# nrfdongle.net
KiCad netlist of a schematic drawn in EAGLE
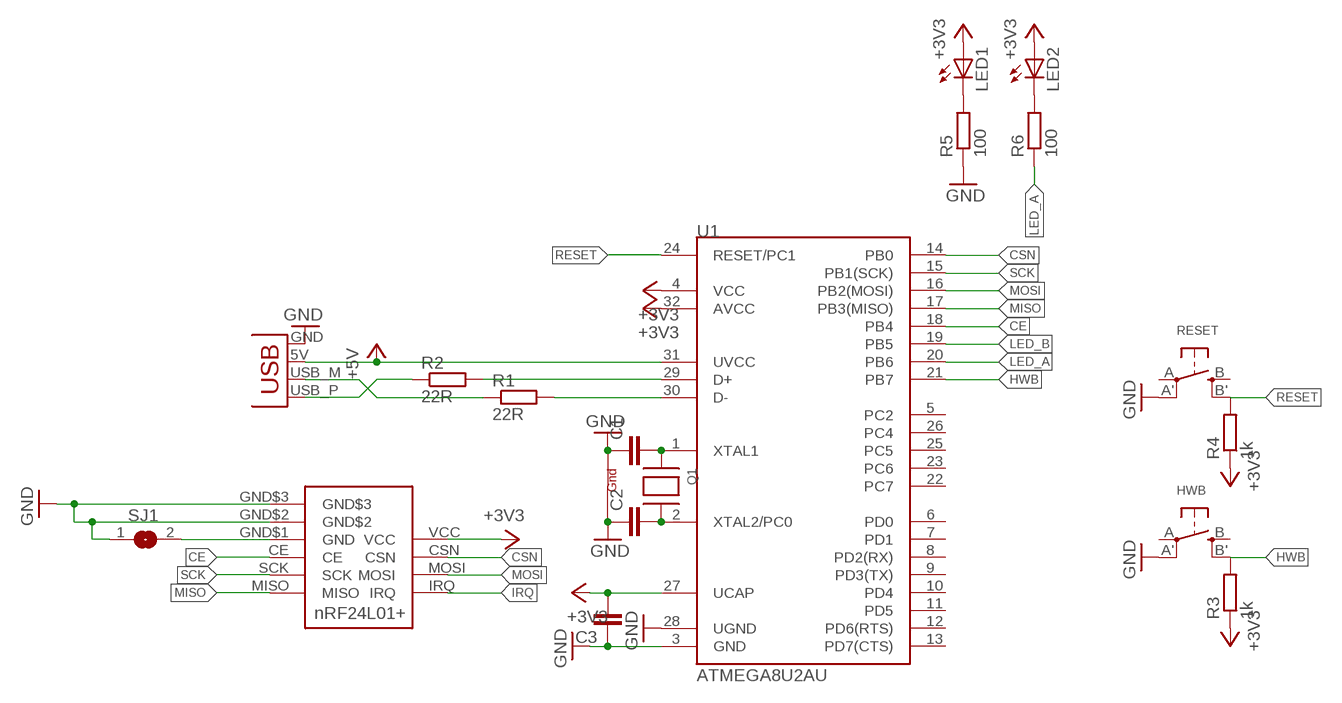
[diagram p0: schematic, sheet 1]

(export (version "E")
  (design (tool "Eeschema 10.0.6"))
  (components
    (comp (ref "C1")
      (value "C-EUC0805")
      (footprint "eagle-import:C0805")
      (libsource (lib "eagle-import") (part "C-EUC0805"))
    )
    (comp (ref "C2")
      (value "C-EUC0805")
      (footprint "eagle-import:C0805")
      (libsource (lib "eagle-import") (part "C-EUC0805"))
    )
    (comp (ref "C3")
      (value "C-EUC0805")
      (footprint "eagle-import:C0805")
      (libsource (lib "eagle-import") (part "C-EUC0805"))
    )
    (comp (ref "CHINESE1")
      (value "NRF24L01+CHINESE-DUAL")
      (footprint "eagle-import:CHINESE-DUALPINOUT")
      (libsource (lib "eagle-import") (part "NRF24L01+CHINESE-DUAL"))
    )
    (comp (ref "HWB")
      (value "SWITCH_TACT_SMT")
      (footprint "eagle-import:EVQ-Q2")
      (libsource (lib "eagle-import") (part "SWITCH_TACT_SMT"))
    )
    (comp (ref "LED1")
      (value "LEDSML0805")
      (footprint "eagle-import:SML0805")
      (libsource (lib "eagle-import") (part "LEDSML0805"))
    )
    (comp (ref "LED2")
      (value "LEDSML0805")
      (footprint "eagle-import:SML0805")
      (libsource (lib "eagle-import") (part "LEDSML0805"))
    )
    (comp (ref "Q1")
      (value "XTAL-4-3225")
      (footprint "eagle-import:NX3225")
      (libsource (lib "eagle-import") (part "XTAL-4-3225"))
    )
    (comp (ref "R1")
      (value "22R")
      (footprint "eagle-import:R0805")
      (libsource (lib "eagle-import") (part "R-EU_R0805"))
    )
    (comp (ref "R2")
      (value "22R")
      (footprint "eagle-import:R0805")
      (libsource (lib "eagle-import") (part "R-EU_R0805"))
    )
    (comp (ref "R3")
      (value "1k")
      (footprint "eagle-import:R0805")
      (libsource (lib "eagle-import") (part "R-EU_R0805"))
    )
    (comp (ref "R4")
      (value "1k")
      (footprint "eagle-import:R0805")
      (libsource (lib "eagle-import") (part "R-EU_R0805"))
    )
    (comp (ref "R5")
      (value "100")
      (footprint "eagle-import:R0805")
      (libsource (lib "eagle-import") (part "R-EU_R0805"))
    )
    (comp (ref "R6")
      (value "100")
      (footprint "eagle-import:R0805")
      (libsource (lib "eagle-import") (part "R-EU_R0805"))
    )
    (comp (ref "RESET")
      (value "SWITCH_TACT_SMT")
      (footprint "eagle-import:EVQ-Q2")
      (libsource (lib "eagle-import") (part "SWITCH_TACT_SMT"))
    )
    (comp (ref "SJ1") (value "SJ") (footprint "eagle-import:SJ") (libsource (lib "eagle-import") (part "SJ")))
    (comp (ref "U1")
      (value "ATMEGA8U2AU")
      (footprint "eagle-import:TQFP32-08")
      (libsource (lib "eagle-import") (part "ATMEGA8U2AU"))
    )
    (comp (ref "X1")
      (value "USBPCB")
      (footprint "eagle-import:USB-A-PCB")
      (libsource (lib "eagle-import") (part "USBPCB"))
    )
  )
  (nets
    (net (code "1") (name "+3V3") (class "Default")
      (node (ref "C3") (pin "2") (pinfunction "2_2") (pintype "passive"))
      (node (ref "CHINESE1") (pin "VCC") (pinfunction "VCC_VCC") (pintype "bidirectional"))
      (node (ref "LED1") (pin "A") (pinfunction "A_A") (pintype "passive"))
      (node (ref "LED2") (pin "A") (pinfunction "A_A") (pintype "passive"))
      (node (ref "R3") (pin "1") (pinfunction "1_1") (pintype "passive"))
      (node (ref "R4") (pin "1") (pinfunction "1_1") (pintype "passive"))
      (node (ref "U1") (pin "27") (pinfunction "UCAP_27") (pintype "bidirectional"))
      (node (ref "U1") (pin "32") (pinfunction "AVCC_32") (pintype "bidirectional"))
      (node (ref "U1") (pin "4") (pinfunction "VCC_4") (pintype "bidirectional"))
    )
    (net (code "2") (name "+5V") (class "Default")
      (node (ref "U1") (pin "31") (pinfunction "UVCC_31") (pintype "bidirectional"))
      (node (ref "X1") (pin "5V") (pinfunction "VBUS_5V") (pintype "bidirectional"))
    )
    (net (code "3") (name "CE") (class "Default")
      (node (ref "CHINESE1") (pin "CE") (pinfunction "CE_CE") (pintype "bidirectional"))
      (node (ref "U1") (pin "18") (pinfunction "PB4_18") (pintype "bidirectional"))
    )
    (net (code "4") (name "CSN") (class "Default")
      (node (ref "CHINESE1") (pin "CSN") (pinfunction "CSN_CSN") (pintype "bidirectional"))
      (node (ref "U1") (pin "14") (pinfunction "PB0_14") (pintype "bidirectional"))
    )
    (net (code "5") (name "GND") (class "Default")
      (node (ref "C1") (pin "1") (pinfunction "1_1") (pintype "passive"))
      (node (ref "C2") (pin "1") (pinfunction "1_1") (pintype "passive"))
      (node (ref "C3") (pin "1") (pinfunction "1_1") (pintype "passive"))
      (node (ref "CHINESE1") (pin "GND$2") (pinfunction "GND$2_GND$2") (pintype "bidirectional"))
      (node (ref "CHINESE1") (pin "GND$3") (pinfunction "GND$3_GND$3") (pintype "bidirectional"))
      (node (ref "HWB") (pin "A'") (pinfunction "P1_A'") (pintype "passive"))
      (node (ref "Q1") (pin "2") (pinfunction "G1_2") (pintype "power_in"))
      (node (ref "Q1") (pin "4") (pinfunction "G2_4") (pintype "power_in"))
      (node (ref "R5") (pin "1") (pinfunction "1_1") (pintype "passive"))
      (node (ref "RESET") (pin "A'") (pinfunction "P1_A'") (pintype "passive"))
      (node (ref "SJ1") (pin "1") (pinfunction "1_1") (pintype "passive"))
      (node (ref "U1") (pin "28") (pinfunction "UGND_28") (pintype "bidirectional"))
      (node (ref "U1") (pin "3") (pinfunction "GND_3") (pintype "bidirectional"))
      (node (ref "X1") (pin "GND") (pinfunction "GND_GND") (pintype "bidirectional"))
    )
    (net (code "6") (name "HWB") (class "Default")
      (node (ref "HWB") (pin "B'") (pinfunction "S1_B'") (pintype "passive"))
      (node (ref "R3") (pin "2") (pinfunction "2_2") (pintype "passive"))
      (node (ref "U1") (pin "21") (pinfunction "PB7_21") (pintype "bidirectional"))
    )
    (net (code "7") (name "IRQ") (class "Default")
      (node (ref "CHINESE1") (pin "IRQ") (pinfunction "IRQ_IRQ") (pintype "bidirectional"))
    )
    (net (code "8") (name "LED_A") (class "Default")
      (node (ref "R6") (pin "1") (pinfunction "1_1") (pintype "passive"))
      (node (ref "U1") (pin "20") (pinfunction "PB6_20") (pintype "bidirectional"))
    )
    (net (code "9") (name "LED_B") (class "Default")
      (node (ref "U1") (pin "19") (pinfunction "PB5_19") (pintype "bidirectional"))
    )
    (net (code "10") (name "MISO") (class "Default")
      (node (ref "CHINESE1") (pin "MISO") (pinfunction "MISO_MISO") (pintype "bidirectional"))
      (node (ref "U1") (pin "17") (pinfunction "PB3(MISO)_17") (pintype "bidirectional"))
    )
    (net (code "11") (name "MOSI") (class "Default")
      (node (ref "CHINESE1") (pin "MOSI") (pinfunction "MOSI_MOSI") (pintype "bidirectional"))
      (node (ref "U1") (pin "16") (pinfunction "PB2(MOSI)_16") (pintype "bidirectional"))
    )
    (net (code "12") (name "Net-(CHINESE1-GND)") (class "Default")
      (node (ref "CHINESE1") (pin "GND$1") (pinfunction "GND_GND$1") (pintype "bidirectional"))
      (node (ref "SJ1") (pin "2") (pinfunction "2_2") (pintype "passive"))
    )
    (net (code "13") (name "Net-(LED1-PadC)") (class "Default")
      (node (ref "LED1") (pin "C") (pinfunction "C_C") (pintype "passive"))
      (node (ref "R5") (pin "2") (pinfunction "2_2") (pintype "passive"))
    )
    (net (code "14") (name "Net-(LED2-PadC)") (class "Default")
      (node (ref "LED2") (pin "C") (pinfunction "C_C") (pintype "passive"))
      (node (ref "R6") (pin "2") (pinfunction "2_2") (pintype "passive"))
    )
    (net (code "15") (name "Net-(Q1-X1)") (class "Default")
      (node (ref "C1") (pin "2") (pinfunction "2_2") (pintype "passive"))
      (node (ref "Q1") (pin "1") (pinfunction "X1_1") (pintype "bidirectional"))
      (node (ref "U1") (pin "1") (pinfunction "XTAL1_1") (pintype "bidirectional"))
    )
    (net (code "16") (name "Net-(Q1-X2)") (class "Default")
      (node (ref "C2") (pin "2") (pinfunction "2_2") (pintype "passive"))
      (node (ref "Q1") (pin "3") (pinfunction "X2_3") (pintype "bidirectional"))
      (node (ref "U1") (pin "2") (pinfunction "XTAL2/PC0_2") (pintype "bidirectional"))
    )
    (net (code "17") (name "Net-(U1-D+)") (class "Default")
      (node (ref "R2") (pin "2") (pinfunction "2_2") (pintype "passive"))
      (node (ref "U1") (pin "29") (pinfunction "D+_29") (pintype "bidirectional"))
    )
    (net (code "18") (name "Net-(U1-D-)") (class "Default")
      (node (ref "R1") (pin "2") (pinfunction "2_2") (pintype "passive"))
      (node (ref "U1") (pin "30") (pinfunction "D-_30") (pintype "bidirectional"))
    )
    (net (code "19") (name "Net-(X1-D+)") (class "Default")
      (node (ref "R2") (pin "1") (pinfunction "1_1") (pintype "passive"))
      (node (ref "X1") (pin "USB_P") (pinfunction "D+_USB_P") (pintype "bidirectional"))
    )
    (net (code "20") (name "Net-(X1-D-)") (class "Default")
      (node (ref "R1") (pin "1") (pinfunction "1_1") (pintype "passive"))
      (node (ref "X1") (pin "USB_M") (pinfunction "D-_USB_M") (pintype "bidirectional"))
    )
    (net (code "21") (name "RESET") (class "Default")
      (node (ref "R4") (pin "2") (pinfunction "2_2") (pintype "passive"))
      (node (ref "RESET") (pin "B'") (pinfunction "S1_B'") (pintype "passive"))
      (node (ref "U1") (pin "24") (pinfunction "RESET/PC1_24") (pintype "bidirectional"))
    )
    (net (code "22") (name "SCK") (class "Default")
      (node (ref "CHINESE1") (pin "SCK") (pinfunction "SCK_SCK") (pintype "bidirectional"))
      (node (ref "U1") (pin "15") (pinfunction "PB1(SCK)_15") (pintype "bidirectional"))
    )
    (net (code "23") (name "unconnected-(HWB-P-PadA)") (class "Default")
      (node (ref "HWB") (pin "A") (pinfunction "P_A") (pintype "passive"))
    )
    (net (code "24") (name "unconnected-(HWB-S-PadB)") (class "Default")
      (node (ref "HWB") (pin "B") (pinfunction "S_B") (pintype "passive"))
    )
    (net (code "25") (name "unconnected-(RESET-P-PadA)") (class "Default")
      (node (ref "RESET") (pin "A") (pinfunction "P_A") (pintype "passive"))
    )
    (net (code "26") (name "unconnected-(RESET-S-PadB)") (class "Default")
      (node (ref "RESET") (pin "B") (pinfunction "S_B") (pintype "passive"))
    )
    (net (code "27") (name "unconnected-(U1-PC2-Pad5)") (class "Default")
      (node (ref "U1") (pin "5") (pinfunction "PC2_5") (pintype "bidirectional"))
    )
    (net (code "28") (name "unconnected-(U1-PC4-Pad26)") (class "Default")
      (node (ref "U1") (pin "26") (pinfunction "PC4_26") (pintype "bidirectional"))
    )
    (net (code "29") (name "unconnected-(U1-PC5-Pad25)") (class "Default")
      (node (ref "U1") (pin "25") (pinfunction "PC5_25") (pintype "bidirectional"))
    )
    (net (code "30") (name "unconnected-(U1-PC6-Pad23)") (class "Default")
      (node (ref "U1") (pin "23") (pinfunction "PC6_23") (pintype "bidirectional"))
    )
    (net (code "31") (name "unconnected-(U1-PC7-Pad22)") (class "Default")
      (node (ref "U1") (pin "22") (pinfunction "PC7_22") (pintype "bidirectional"))
    )
    (net (code "32") (name "unconnected-(U1-PD0-Pad6)") (class "Default")
      (node (ref "U1") (pin "6") (pinfunction "PD0_6") (pintype "bidirectional"))
    )
    (net (code "33") (name "unconnected-(U1-PD1-Pad7)") (class "Default")
      (node (ref "U1") (pin "7") (pinfunction "PD1_7") (pintype "bidirectional"))
    )
    (net (code "34") (name "unconnected-(U1-PD2(RX)-Pad8)") (class "Default")
      (node (ref "U1") (pin "8") (pinfunction "PD2(RX)_8") (pintype "bidirectional"))
    )
    (net (code "35") (name "unconnected-(U1-PD3(TX)-Pad9)") (class "Default")
      (node (ref "U1") (pin "9") (pinfunction "PD3(TX)_9") (pintype "bidirectional"))
    )
    (net (code "36") (name "unconnected-(U1-PD4-Pad10)") (class "Default")
      (node (ref "U1") (pin "10") (pinfunction "PD4_10") (pintype "bidirectional"))
    )
    (net (code "37") (name "unconnected-(U1-PD5-Pad11)") (class "Default")
      (node (ref "U1") (pin "11") (pinfunction "PD5_11") (pintype "bidirectional"))
    )
    (net (code "38") (name "unconnected-(U1-PD6(RTS)-Pad12)") (class "Default")
      (node (ref "U1") (pin "12") (pinfunction "PD6(RTS)_12") (pintype "bidirectional"))
    )
    (net (code "39") (name "unconnected-(U1-PD7(CTS)-Pad13)") (class "Default")
      (node (ref "U1") (pin "13") (pinfunction "PD7(CTS)_13") (pintype "bidirectional"))
    )
  )
)
